# 1-Schematic_CessnaCitationX_Center.net
KiCad netlist of a schematic drawn in EasyEDA
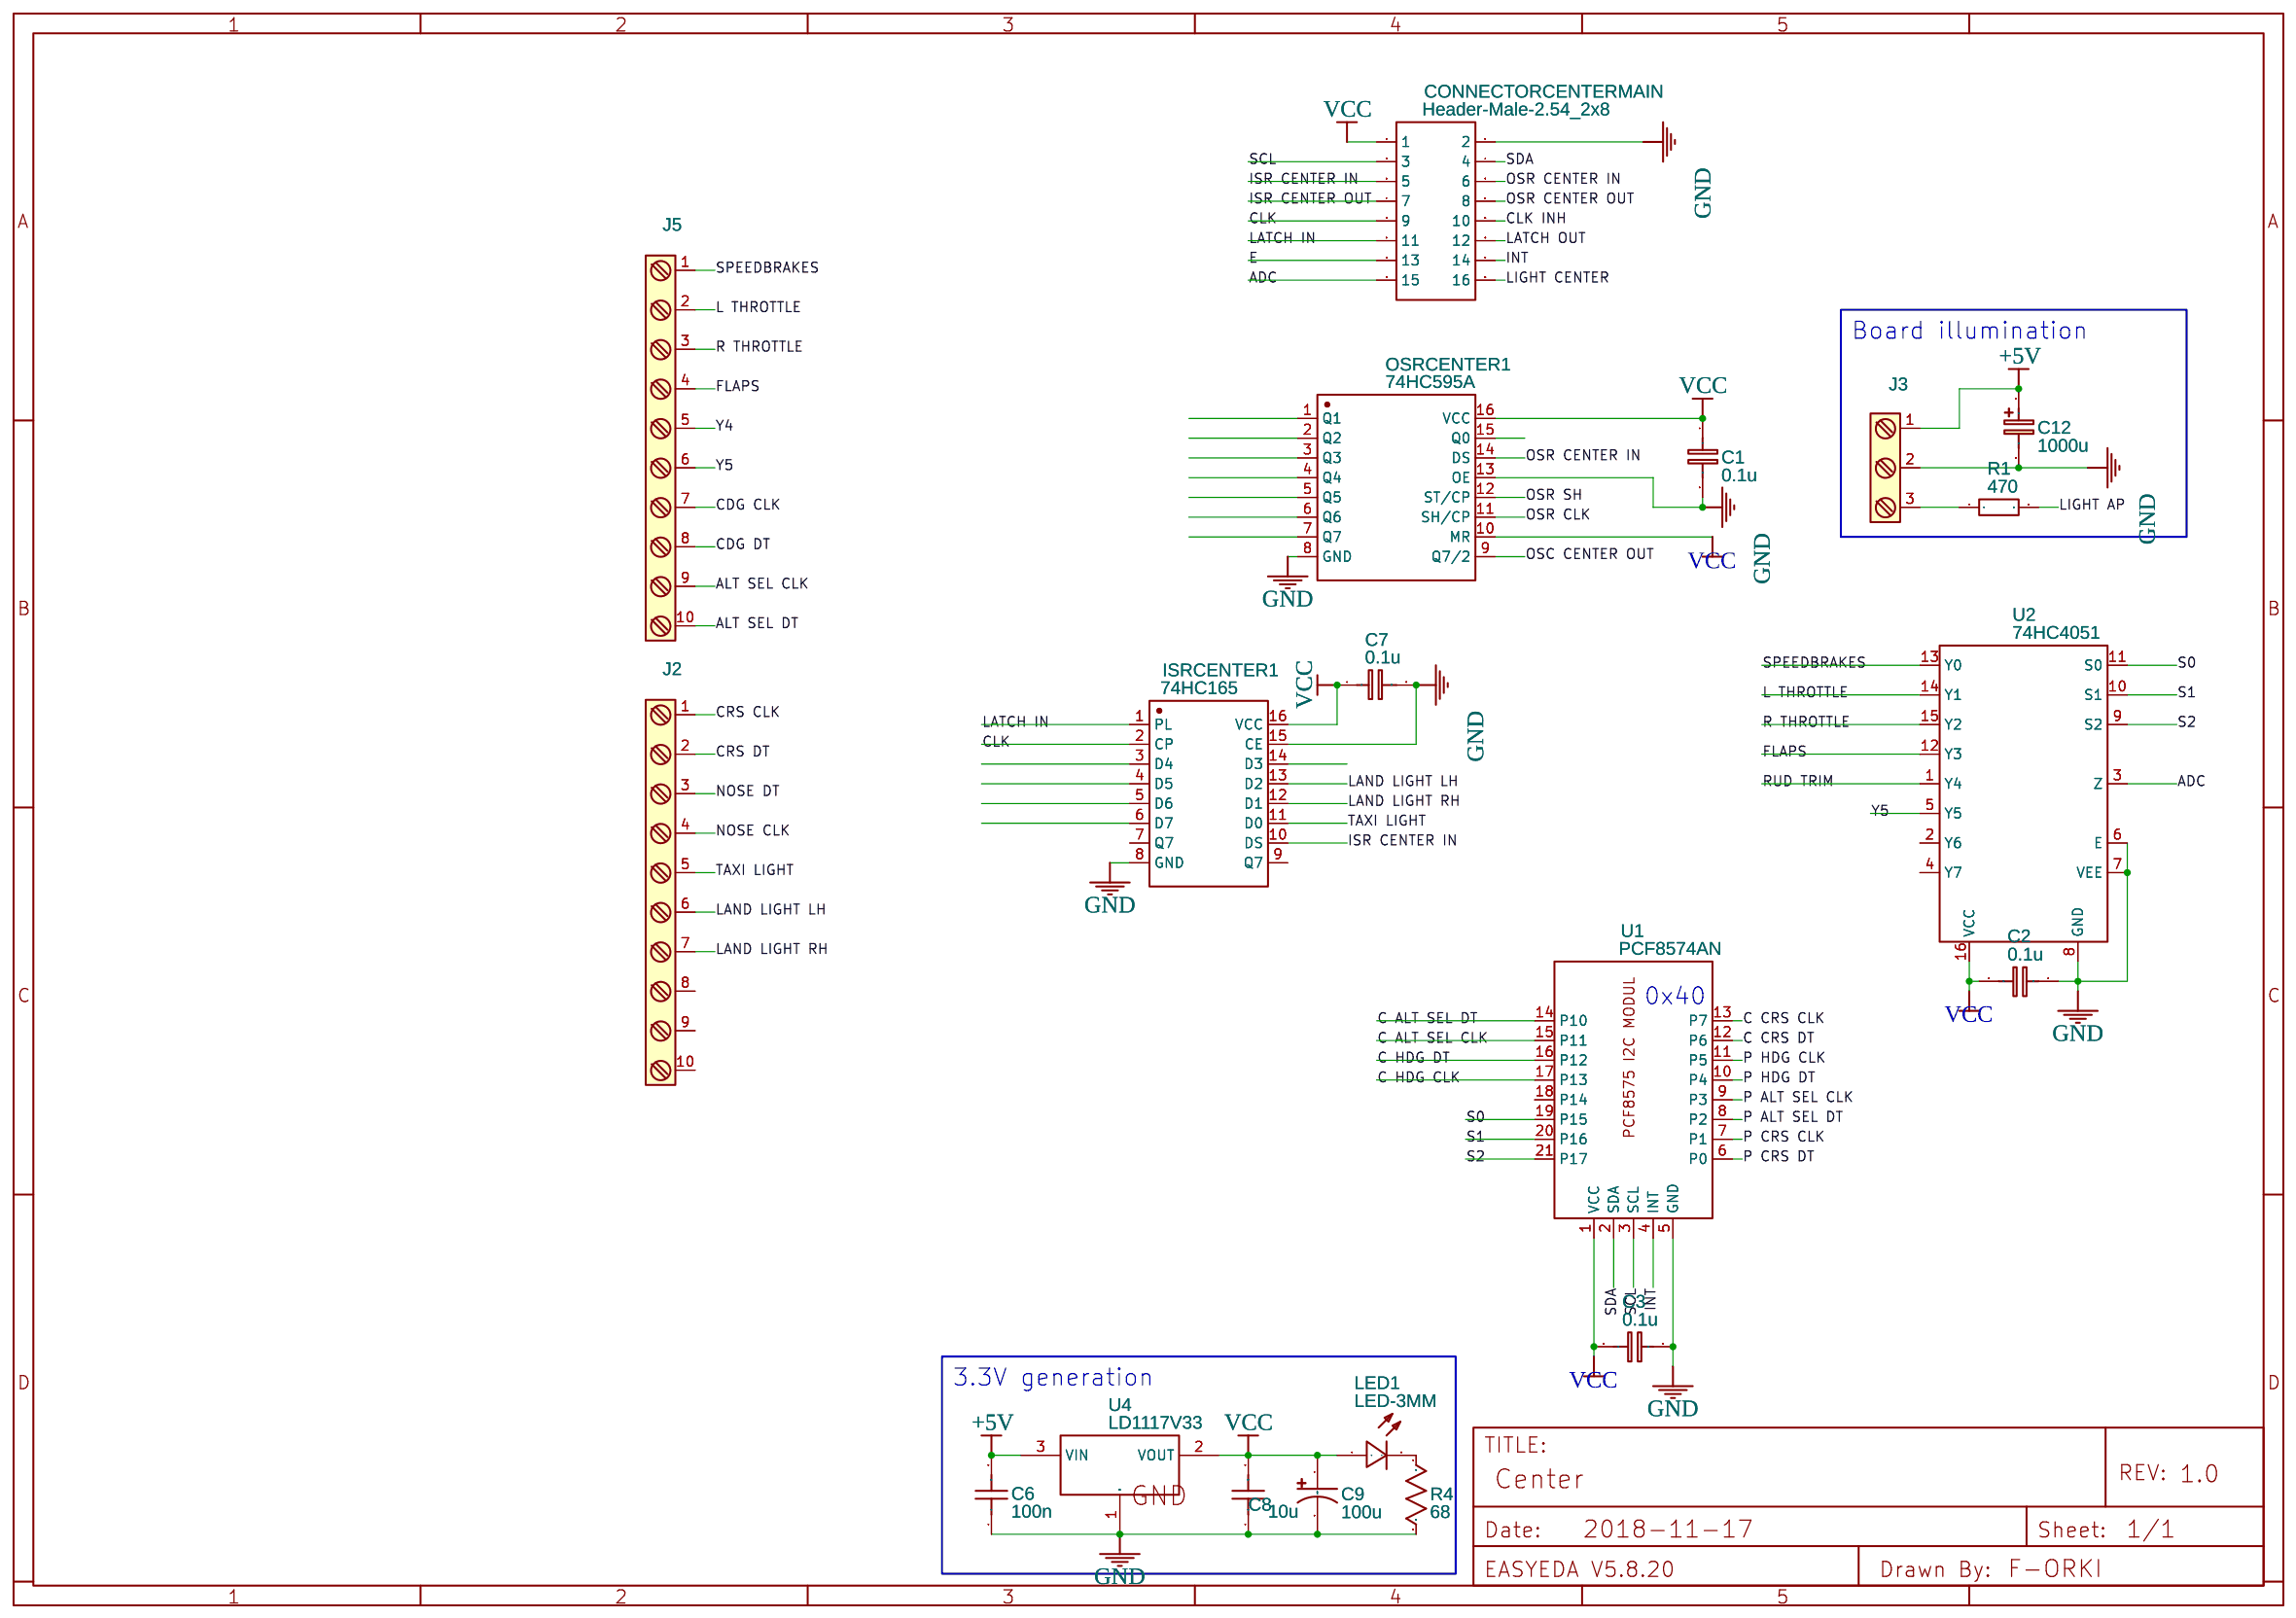
[diagram p0: schematic sheet]

(export (version "E")
  (design (tool "Eeschema 10.0.6"))
  (components
    (comp (ref "C1")
      (value "0.1u")
      (fields (field (name "BOM_Manufacturer Part") "?"))
      (libsource (lib "") (part "Cap_RAD-0.1_EU_1"))
    )
    (comp (ref "C2")
      (value "0.1u")
      (fields (field (name "BOM_Manufacturer Part") "?"))
      (libsource (lib "") (part "Cap_RAD-0.1_EU_3"))
    )
    (comp (ref "C3")
      (value "0.1u")
      (fields (field (name "BOM_Manufacturer Part") "?"))
      (libsource (lib "") (part "Cap_RAD-0.1_EU_2"))
    )
    (comp (ref "C6")
      (value "100n")
      (fields (field (name "BOM_Manufacturer Part") "?"))
      (libsource (lib "") (part "Cap_RAD-0.1_US"))
    )
    (comp (ref "C7")
      (value "0.1u")
      (fields (field (name "BOM_Manufacturer Part") "?"))
      (libsource (lib "") (part "Cap_RAD-0.1_EU"))
    )
    (comp (ref "C8")
      (value "10u")
      (fields (field (name "BOM_Manufacturer Part") "?"))
      (libsource (lib "") (part "Cap_RAD-0.1_US"))
    )
    (comp (ref "C9")
      (value "100u")
      (fields (field (name "BOM_Manufacturer Part") "?"))
      (libsource (lib "") (part "Cap_Electrolytic(TH)_D3.0XF1.5_US"))
    )
    (comp (ref "C12")
      (value "1000u")
      (fields (field (name "BOM_Manufacturer Part") "?"))
      (libsource (lib "") (part "Cap_Electrolytic(TH)_D3.0XF1.5_EU"))
    )
    (comp (ref "CONNECTORCENTERMAIN")
      (value "Header-Male-2.54_2x8")
      (fields
        (field (name "BOM_Manufacturer Part") "Double row straight 2*8Headers  Pins 2.54mm")
        (field (name "BOM_Supplier Part") "C68234")
      )
      (libsource (lib "") (part "Unknown_720_100"))
    )
    (comp (ref "ISRCENTER1")
      (value "74HC165")
      (fields
        (field (name "BOM_Manufacturer Part") "74HC165D,653")
        (field (name "BOM_Supplier Part") "C5613")
      )
      (libsource (lib "") (part "Unknown_605_350"))
    )
    (comp (ref "J2")
      (value "Screw_Terminal_1x10")
      (fields (field (name "BOM_Manufacturer Part") "?"))
      (libsource (lib "") (part "Unknown_335_355"))
    )
    (comp (ref "J3")
      (value "Screw_Terminal_1x03")
      (fields (field (name "BOM_Manufacturer Part") "?"))
      (libsource (lib "") (part "Unknown_955_230"))
    )
    (comp (ref "J5")
      (value "Screw_Terminal_1x10")
      (fields (field (name "BOM_Manufacturer Part") "?"))
      (libsource (lib "") (part "Unknown_335_130"))
    )
    (comp (ref "LED1")
      (value "LED-3MM")
      (fields
        (field (name "BOM_Manufacturer Part") "204-10SURD/S530-A3")
        (field (name "BOM_Supplier Part") "C99772")
      )
      (libsource (lib "") (part "Unknown_690_725"))
    )
    (comp (ref "OSRCENTER1")
      (value "74HC595A")
      (fields (field (name "BOM_Supplier Part") "C110383"))
      (libsource (lib "") (part "Unknown_700_195"))
    )
    (comp (ref "R1")
      (value "470")
      (fields (field (name "BOM_Manufacturer Part") "?"))
      (libsource (lib "") (part "Res_AXIAL-0.3(1/8W)_EU"))
    )
    (comp (ref "R4")
      (value "68")
      (fields (field (name "BOM_Manufacturer Part") "?"))
      (libsource (lib "") (part "Res_AXIAL-0.3(1/8W)_US"))
    )
    (comp (ref "U1")
      (value "PCF8574AN")
      (fields (field (name "BOM_Manufacturer Part") "?"))
      (libsource (lib "") (part "Unknown_760_490"))
    )
    (comp (ref "U2")
      (value "74HC4051")
      (fields (field (name "BOM_Manufacturer Part") "?"))
      (libsource (lib "") (part "Unknown_1020_390"))
    )
    (comp (ref "U4")
      (value "LD1117V33")
      (fields (field (name "BOM_Supplier Part") "C283467"))
      (libsource (lib "") (part "Unknown_560_750"))
    )
  )
  (nets
    (net (code "1") (name "+5V") (class "Default")
      (node (ref "C12") (pin "1") (pinfunction "1_1") (pintype "unspecified"))
      (node (ref "C6") (pin "2") (pinfunction "2_2") (pintype "unspecified"))
      (node (ref "J3") (pin "1") (pintype "unspecified"))
      (node (ref "U4") (pin "3") (pinfunction "VIN_3") (pintype "passive"))
    )
    (net (code "2") (name "/ADC") (class "Default")
      (node (ref "CONNECTORCENTERMAIN") (pin "15") (pinfunction "15_15") (pintype "input"))
      (node (ref "U2") (pin "3") (pinfunction "Z_3") (pintype "unspecified"))
    )
    (net (code "3") (name "/ALT SEL CLK") (class "Default")
      (node (ref "J5") (pin "9") (pintype "unspecified"))
    )
    (net (code "4") (name "/ALT SEL DT") (class "Default")
      (node (ref "J5") (pin "10") (pintype "unspecified"))
    )
    (net (code "5") (name "/C ALT SEL CLK") (class "Default")
      (node (ref "U1") (pin "15") (pinfunction "P11_15") (pintype "unspecified"))
    )
    (net (code "6") (name "/C ALT SEL DT") (class "Default")
      (node (ref "U1") (pin "14") (pinfunction "P10_14") (pintype "unspecified"))
    )
    (net (code "7") (name "/C CRS CLK") (class "Default")
      (node (ref "U1") (pin "13") (pinfunction "P7_13") (pintype "unspecified"))
    )
    (net (code "8") (name "/C CRS DT") (class "Default")
      (node (ref "U1") (pin "12") (pinfunction "P6_12") (pintype "unspecified"))
    )
    (net (code "9") (name "/C HDG CLK") (class "Default")
      (node (ref "U1") (pin "17") (pinfunction "P13_17") (pintype "unspecified"))
    )
    (net (code "10") (name "/C HDG DT") (class "Default")
      (node (ref "U1") (pin "16") (pinfunction "P12_16") (pintype "unspecified"))
    )
    (net (code "11") (name "/CDG CLK") (class "Default") (node (ref "J5") (pin "7") (pintype "unspecified")))
    (net (code "12") (name "/CDG DT") (class "Default") (node (ref "J5") (pin "8") (pintype "unspecified")))
    (net (code "13") (name "/CLK") (class "Default")
      (node (ref "CONNECTORCENTERMAIN") (pin "9") (pinfunction "9_9") (pintype "input"))
      (node (ref "ISRCENTER1") (pin "2") (pinfunction "CP_2") (pintype "unspecified"))
    )
    (net (code "14") (name "/CLK INH") (class "Default")
      (node (ref "CONNECTORCENTERMAIN") (pin "10") (pinfunction "10_10") (pintype "input"))
    )
    (net (code "15") (name "/CRS CLK") (class "Default") (node (ref "J2") (pin "1") (pintype "unspecified")))
    (net (code "16") (name "/CRS DT") (class "Default") (node (ref "J2") (pin "2") (pintype "unspecified")))
    (net (code "17") (name "/E") (class "Default")
      (node (ref "CONNECTORCENTERMAIN") (pin "13") (pinfunction "13_13") (pintype "input"))
    )
    (net (code "18") (name "/FLAPS") (class "Default")
      (node (ref "J5") (pin "4") (pintype "unspecified"))
      (node (ref "U2") (pin "12") (pinfunction "Y3_12") (pintype "unspecified"))
    )
    (net (code "19") (name "/INT") (class "Default")
      (node (ref "CONNECTORCENTERMAIN") (pin "14") (pinfunction "14_14") (pintype "input"))
      (node (ref "U1") (pin "4") (pinfunction "INT_4") (pintype "unspecified"))
    )
    (net (code "20") (name "/ISR CENTER IN") (class "Default")
      (node (ref "CONNECTORCENTERMAIN") (pin "5") (pinfunction "5_5") (pintype "input"))
      (node (ref "ISRCENTER1") (pin "10") (pinfunction "DS_10") (pintype "unspecified"))
    )
    (net (code "21") (name "/ISR CENTER OUT") (class "Default")
      (node (ref "CONNECTORCENTERMAIN") (pin "7") (pinfunction "7_7") (pintype "input"))
    )
    (net (code "22") (name "/L THROTTLE") (class "Default")
      (node (ref "J5") (pin "2") (pintype "unspecified"))
      (node (ref "U2") (pin "14") (pinfunction "Y1_14") (pintype "unspecified"))
    )
    (net (code "23") (name "/LAND LIGHT LH") (class "Default")
      (node (ref "ISRCENTER1") (pin "13") (pinfunction "D2_13") (pintype "unspecified"))
      (node (ref "J2") (pin "6") (pintype "unspecified"))
    )
    (net (code "24") (name "/LAND LIGHT RH") (class "Default")
      (node (ref "ISRCENTER1") (pin "12") (pinfunction "D1_12") (pintype "unspecified"))
      (node (ref "J2") (pin "7") (pintype "unspecified"))
    )
    (net (code "25") (name "/LATCH IN") (class "Default")
      (node (ref "CONNECTORCENTERMAIN") (pin "11") (pinfunction "11_11") (pintype "input"))
      (node (ref "ISRCENTER1") (pin "1") (pinfunction "PL_1") (pintype "unspecified"))
    )
    (net (code "26") (name "/LATCH OUT") (class "Default")
      (node (ref "CONNECTORCENTERMAIN") (pin "12") (pinfunction "12_12") (pintype "input"))
    )
    (net (code "27") (name "/LIGHT AP") (class "Default")
      (node (ref "R1") (pin "2") (pinfunction "2_2") (pintype "unspecified"))
    )
    (net (code "28") (name "/LIGHT CENTER") (class "Default")
      (node (ref "CONNECTORCENTERMAIN") (pin "16") (pinfunction "16_16") (pintype "input"))
    )
    (net (code "29") (name "/NOSE CLK") (class "Default") (node (ref "J2") (pin "4") (pintype "unspecified")))
    (net (code "30") (name "/NOSE DT") (class "Default") (node (ref "J2") (pin "3") (pintype "unspecified")))
    (net (code "31") (name "/OSC CENTER OUT") (class "Default")
      (node (ref "OSRCENTER1") (pin "9") (pinfunction "Q7/2_9") (pintype "unspecified"))
    )
    (net (code "32") (name "/OSR CENTER IN") (class "Default")
      (node (ref "CONNECTORCENTERMAIN") (pin "6") (pinfunction "6_6") (pintype "input"))
      (node (ref "OSRCENTER1") (pin "14") (pinfunction "DS_14") (pintype "unspecified"))
    )
    (net (code "33") (name "/OSR CENTER OUT") (class "Default")
      (node (ref "CONNECTORCENTERMAIN") (pin "8") (pinfunction "8_8") (pintype "input"))
    )
    (net (code "34") (name "/OSR CLK") (class "Default")
      (node (ref "OSRCENTER1") (pin "11") (pinfunction "SH/CP_11") (pintype "unspecified"))
    )
    (net (code "35") (name "/OSR SH") (class "Default")
      (node (ref "OSRCENTER1") (pin "12") (pinfunction "ST/CP_12") (pintype "unspecified"))
    )
    (net (code "36") (name "/P ALT SEL CLK") (class "Default")
      (node (ref "U1") (pin "9") (pinfunction "P3_9") (pintype "unspecified"))
    )
    (net (code "37") (name "/P ALT SEL DT") (class "Default")
      (node (ref "U1") (pin "8") (pinfunction "P2_8") (pintype "unspecified"))
    )
    (net (code "38") (name "/P CRS CLK") (class "Default")
      (node (ref "U1") (pin "7") (pinfunction "P1_7") (pintype "unspecified"))
    )
    (net (code "39") (name "/P CRS DT") (class "Default")
      (node (ref "U1") (pin "6") (pinfunction "P0_6") (pintype "unspecified"))
    )
    (net (code "40") (name "/P HDG CLK") (class "Default")
      (node (ref "U1") (pin "11") (pinfunction "P5_11") (pintype "unspecified"))
    )
    (net (code "41") (name "/P HDG DT") (class "Default")
      (node (ref "U1") (pin "10") (pinfunction "P4_10") (pintype "unspecified"))
    )
    (net (code "42") (name "/R THROTTLE") (class "Default")
      (node (ref "J5") (pin "3") (pintype "unspecified"))
      (node (ref "U2") (pin "15") (pinfunction "Y2_15") (pintype "unspecified"))
    )
    (net (code "43") (name "/RUD TRIM") (class "Default")
      (node (ref "U2") (pin "1") (pinfunction "Y4_1") (pintype "unspecified"))
    )
    (net (code "44") (name "/S0") (class "Default")
      (node (ref "U1") (pin "19") (pinfunction "P15_19") (pintype "unspecified"))
      (node (ref "U2") (pin "11") (pinfunction "S0_11") (pintype "unspecified"))
    )
    (net (code "45") (name "/S1") (class "Default")
      (node (ref "U1") (pin "20") (pinfunction "P16_20") (pintype "unspecified"))
      (node (ref "U2") (pin "10") (pinfunction "S1_10") (pintype "unspecified"))
    )
    (net (code "46") (name "/S2") (class "Default")
      (node (ref "U1") (pin "21") (pinfunction "P17_21") (pintype "unspecified"))
      (node (ref "U2") (pin "9") (pinfunction "S2_9") (pintype "unspecified"))
    )
    (net (code "47") (name "/SCL") (class "Default")
      (node (ref "CONNECTORCENTERMAIN") (pin "3") (pinfunction "3_3") (pintype "input"))
      (node (ref "U1") (pin "3") (pinfunction "SCL_3") (pintype "unspecified"))
    )
    (net (code "48") (name "/SDA") (class "Default")
      (node (ref "CONNECTORCENTERMAIN") (pin "4") (pinfunction "4_4") (pintype "input"))
      (node (ref "U1") (pin "2") (pinfunction "SDA_2") (pintype "unspecified"))
    )
    (net (code "49") (name "/SPEEDBRAKES") (class "Default")
      (node (ref "J5") (pin "1") (pintype "unspecified"))
      (node (ref "U2") (pin "13") (pinfunction "Y0_13") (pintype "unspecified"))
    )
    (net (code "50") (name "/TAXI LIGHT") (class "Default")
      (node (ref "ISRCENTER1") (pin "11") (pinfunction "D0_11") (pintype "unspecified"))
      (node (ref "J2") (pin "5") (pintype "unspecified"))
    )
    (net (code "51") (name "/Y4") (class "Default") (node (ref "J5") (pin "5") (pintype "unspecified")))
    (net (code "52") (name "/Y5") (class "Default")
      (node (ref "J5") (pin "6") (pintype "unspecified"))
      (node (ref "U2") (pin "5") (pinfunction "Y5_5") (pintype "unspecified"))
    )
    (net (code "53") (name "GND") (class "Default")
      (node (ref "C1") (pin "2") (pinfunction "2_2") (pintype "unspecified"))
      (node (ref "C12") (pin "2") (pinfunction "2_2") (pintype "unspecified"))
      (node (ref "C2") (pin "1") (pinfunction "1_1") (pintype "unspecified"))
      (node (ref "C3") (pin "1") (pinfunction "1_1") (pintype "unspecified"))
      (node (ref "C6") (pin "1") (pinfunction "1_1") (pintype "unspecified"))
      (node (ref "C7") (pin "2") (pinfunction "2_2") (pintype "unspecified"))
      (node (ref "C8") (pin "1") (pinfunction "1_1") (pintype "unspecified"))
      (node (ref "C9") (pin "2") (pinfunction "2_2") (pintype "unspecified"))
      (node (ref "CONNECTORCENTERMAIN") (pin "2") (pinfunction "2_2") (pintype "input"))
      (node (ref "ISRCENTER1") (pin "15") (pinfunction "CE_15") (pintype "unspecified"))
      (node (ref "ISRCENTER1") (pin "8") (pinfunction "GND_8") (pintype "unspecified"))
      (node (ref "J3") (pin "2") (pintype "unspecified"))
      (node (ref "OSRCENTER1") (pin "13") (pinfunction "OE_13") (pintype "unspecified"))
      (node (ref "OSRCENTER1") (pin "8") (pinfunction "GND_8") (pintype "unspecified"))
      (node (ref "R4") (pin "2") (pinfunction "2_2") (pintype "unspecified"))
      (node (ref "U1") (pin "5") (pinfunction "GND_5") (pintype "unspecified"))
      (node (ref "U2") (pin "6") (pinfunction "E_6") (pintype "unspecified"))
      (node (ref "U2") (pin "7") (pinfunction "VEE_7") (pintype "unspecified"))
      (node (ref "U2") (pin "8") (pinfunction "GND_8") (pintype "unspecified"))
      (node (ref "U4") (pin "1") (pinfunction "GND_1") (pintype "unspecified"))
    )
    (net (code "54") (name "Net-(J3-Pad3)") (class "Default")
      (node (ref "J3") (pin "3") (pintype "unspecified"))
      (node (ref "R1") (pin "1") (pinfunction "1_1") (pintype "unspecified"))
    )
    (net (code "55") (name "Net-(LED1--)") (class "Default")
      (node (ref "LED1") (pin "2") (pinfunction "-_2") (pintype "unspecified"))
      (node (ref "R4") (pin "1") (pinfunction "1_1") (pintype "unspecified"))
    )
    (net (code "56") (name "VCC") (class "Default")
      (node (ref "C1") (pin "1") (pinfunction "1_1") (pintype "unspecified"))
      (node (ref "C2") (pin "2") (pinfunction "2_2") (pintype "unspecified"))
      (node (ref "C3") (pin "2") (pinfunction "2_2") (pintype "unspecified"))
      (node (ref "C7") (pin "1") (pinfunction "1_1") (pintype "unspecified"))
      (node (ref "C8") (pin "2") (pinfunction "2_2") (pintype "unspecified"))
      (node (ref "C9") (pin "1") (pinfunction "1_1") (pintype "unspecified"))
      (node (ref "CONNECTORCENTERMAIN") (pin "1") (pinfunction "1_1") (pintype "input"))
      (node (ref "ISRCENTER1") (pin "16") (pinfunction "VCC_16") (pintype "unspecified"))
      (node (ref "LED1") (pin "1") (pinfunction "+_1") (pintype "unspecified"))
      (node (ref "OSRCENTER1") (pin "10") (pinfunction "MR_10") (pintype "unspecified"))
      (node (ref "OSRCENTER1") (pin "16") (pinfunction "VCC_16") (pintype "unspecified"))
      (node (ref "U1") (pin "1") (pinfunction "VCC_1") (pintype "unspecified"))
      (node (ref "U2") (pin "16") (pinfunction "VCC_16") (pintype "unspecified"))
      (node (ref "U4") (pin "2") (pinfunction "VOUT_2") (pintype "passive"))
    )
    (net (code "57") (name "unconnected-(ISRCENTER1-D3-Pad14)") (class "Default")
      (node (ref "ISRCENTER1") (pin "14") (pinfunction "D3_14") (pintype "unspecified"))
    )
    (net (code "58") (name "unconnected-(ISRCENTER1-D4-Pad3)") (class "Default")
      (node (ref "ISRCENTER1") (pin "3") (pinfunction "D4_3") (pintype "unspecified"))
    )
    (net (code "59") (name "unconnected-(ISRCENTER1-D5-Pad4)") (class "Default")
      (node (ref "ISRCENTER1") (pin "4") (pinfunction "D5_4") (pintype "unspecified"))
    )
    (net (code "60") (name "unconnected-(ISRCENTER1-D6-Pad5)") (class "Default")
      (node (ref "ISRCENTER1") (pin "5") (pinfunction "D6_5") (pintype "unspecified"))
    )
    (net (code "61") (name "unconnected-(ISRCENTER1-D7-Pad6)") (class "Default")
      (node (ref "ISRCENTER1") (pin "6") (pinfunction "D7_6") (pintype "unspecified"))
    )
    (net (code "62") (name "unconnected-(ISRCENTER1-Q7-Pad7)") (class "Default")
      (node (ref "ISRCENTER1") (pin "7") (pinfunction "Q7_7") (pintype "unspecified"))
    )
    (net (code "63") (name "unconnected-(ISRCENTER1-Q7-Pad9)") (class "Default")
      (node (ref "ISRCENTER1") (pin "9") (pinfunction "Q7_9") (pintype "unspecified"))
    )
    (net (code "64") (name "unconnected-(J2-Pad8)") (class "Default")
      (node (ref "J2") (pin "8") (pintype "unspecified"))
    )
    (net (code "65") (name "unconnected-(J2-Pad9)") (class "Default")
      (node (ref "J2") (pin "9") (pintype "unspecified"))
    )
    (net (code "66") (name "unconnected-(J2-Pad10)") (class "Default")
      (node (ref "J2") (pin "10") (pintype "unspecified"))
    )
    (net (code "67") (name "unconnected-(OSRCENTER1-Q0-Pad15)") (class "Default")
      (node (ref "OSRCENTER1") (pin "15") (pinfunction "Q0_15") (pintype "unspecified"))
    )
    (net (code "68") (name "unconnected-(OSRCENTER1-Q1-Pad1)") (class "Default")
      (node (ref "OSRCENTER1") (pin "1") (pinfunction "Q1_1") (pintype "unspecified"))
    )
    (net (code "69") (name "unconnected-(OSRCENTER1-Q2-Pad2)") (class "Default")
      (node (ref "OSRCENTER1") (pin "2") (pinfunction "Q2_2") (pintype "unspecified"))
    )
    (net (code "70") (name "unconnected-(OSRCENTER1-Q3-Pad3)") (class "Default")
      (node (ref "OSRCENTER1") (pin "3") (pinfunction "Q3_3") (pintype "unspecified"))
    )
    (net (code "71") (name "unconnected-(OSRCENTER1-Q4-Pad4)") (class "Default")
      (node (ref "OSRCENTER1") (pin "4") (pinfunction "Q4_4") (pintype "unspecified"))
    )
    (net (code "72") (name "unconnected-(OSRCENTER1-Q5-Pad5)") (class "Default")
      (node (ref "OSRCENTER1") (pin "5") (pinfunction "Q5_5") (pintype "unspecified"))
    )
    (net (code "73") (name "unconnected-(OSRCENTER1-Q6-Pad6)") (class "Default")
      (node (ref "OSRCENTER1") (pin "6") (pinfunction "Q6_6") (pintype "unspecified"))
    )
    (net (code "74") (name "unconnected-(OSRCENTER1-Q7-Pad7)") (class "Default")
      (node (ref "OSRCENTER1") (pin "7") (pinfunction "Q7_7") (pintype "unspecified"))
    )
    (net (code "75") (name "unconnected-(U1-P14-Pad18)") (class "Default")
      (node (ref "U1") (pin "18") (pinfunction "P14_18") (pintype "unspecified"))
    )
    (net (code "76") (name "unconnected-(U2-Y6-Pad2)") (class "Default")
      (node (ref "U2") (pin "2") (pinfunction "Y6_2") (pintype "unspecified"))
    )
    (net (code "77") (name "unconnected-(U2-Y7-Pad4)") (class "Default")
      (node (ref "U2") (pin "4") (pinfunction "Y7_4") (pintype "unspecified"))
    )
  )
)
